# Sheet1.net
KiCad netlist of a schematic drawn in Altium Designer
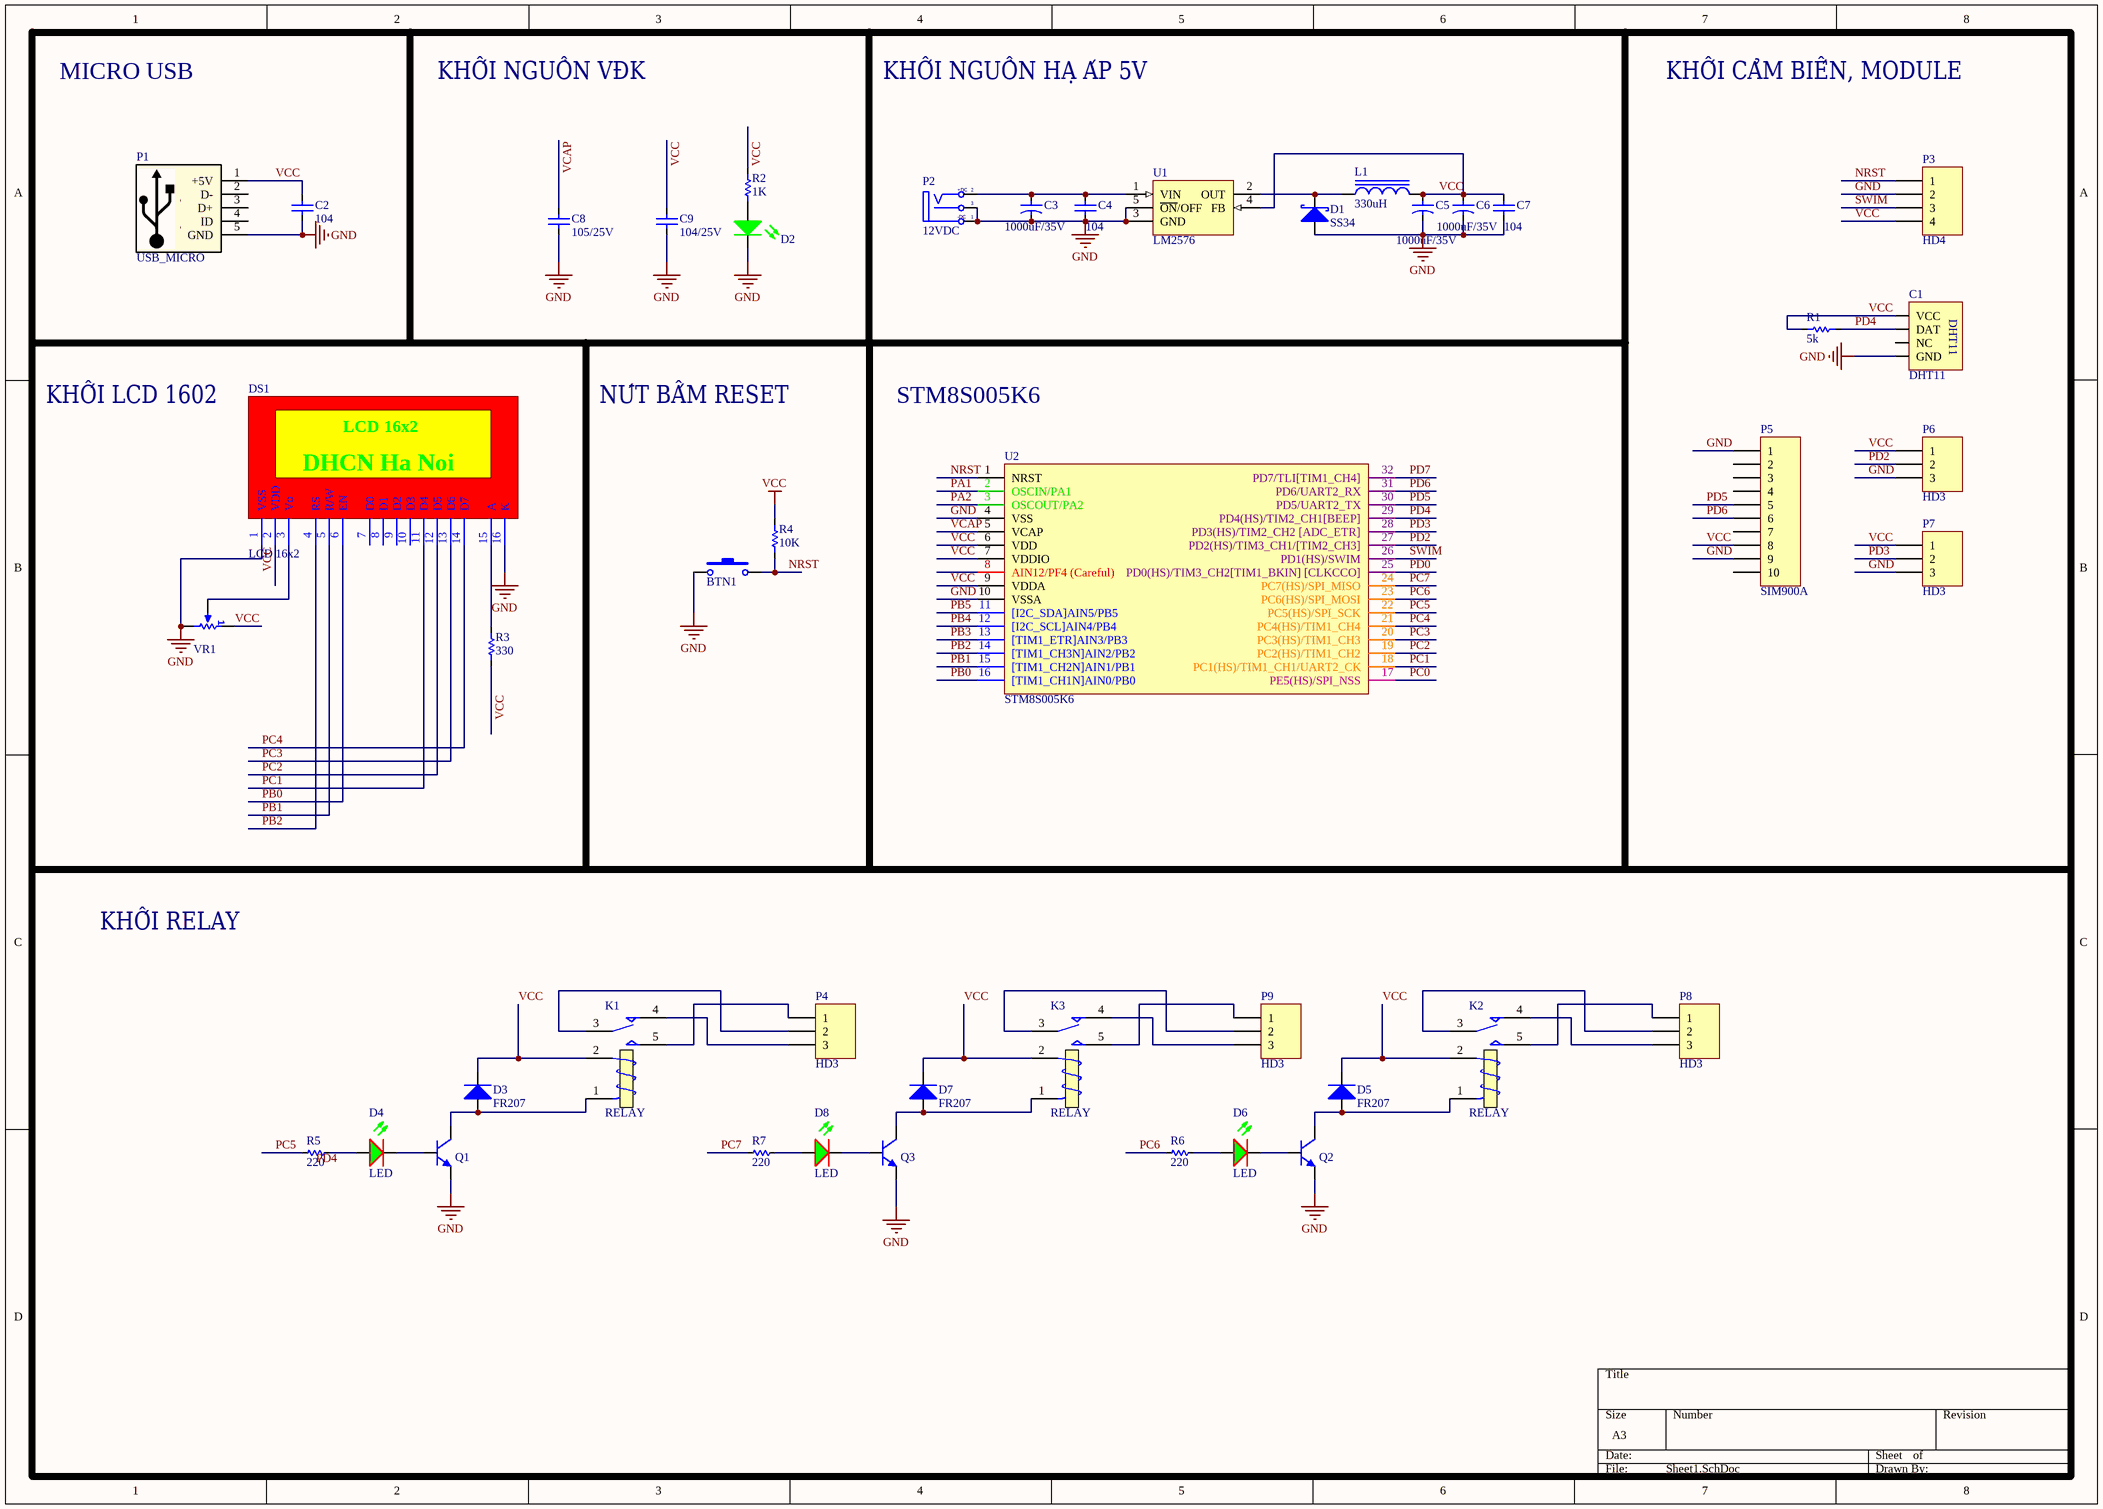
[diagram p0: Sheet1.SchDoc]

(export (version "E")
  (design (tool "Eeschema 10.0.6"))
  (components
    (comp (ref "BTN1")
      (value "BT")
      (footprint "BUTTON SMD MINI")
      (libsource (lib "LIB ALtium") (part "BUTTON"))
    )
    (comp (ref "C1")
      (value "DHT11")
      (footprint "DHT11")
      (fields
        (field (name "MANUFACTURER") "Würth Elektronik eiSos GmbH")
        (field (name "PARTNO") "613004143121")
        (field (name "CREATED BY") "Karrer Zheng")
      )
      (libsource (lib "LIBRARY") (part "DHT11"))
    )
    (comp (ref "C2")
      (value "104")
      (footprint "CAP-0805")
      (description "22pF ±5% 50V Ceramic Capacitor C0G, NP0 0805 (2012 Metric)")
      (fields
        (field (name "MANUFACTURER") "Samsung Electro-Mechanics America, Inc.")
        (field (name "MANUFACTURER PART NUMBER") "CL21B105KOFNNNE")
      )
      (libsource (lib "AltiumLibraryTieuBao") (part "CAP-CER-22pF-50V-0805-10%"))
    )
    (comp (ref "C3")
      (value "1000uF/35V")
      (footprint "CAP 13x25x5")
      (libsource (lib "AltiumLibraryTieuBao_moi") (part "CAP 1000uF/35V"))
    )
    (comp (ref "C4")
      (value "104")
      (footprint "CAP-0603")
      (description "1000pF 50V Ceramic Capacitor X7R 0603 (1608 Metric) 0.063\" L x 0.031\" W (1.60mm x 0.80mm)")
      (fields
        (field (name "MANUFACTURER") "Samsung Electro-Mechanics America, Inc.")
        (field (name "MANUFACTURER PART NUMBER") "CL10B102KB8NNNC")
      )
      (libsource (lib "AltiumLibraryTieuBao_moi") (part "CAP-CER-102-50V-0603-10%_6"))
    )
    (comp (ref "C5")
      (value "1000uF/35V")
      (footprint "CAP 13x25x5")
      (libsource (lib "AltiumLibraryTieuBao_moi") (part "CAP 1000uF/35V"))
    )
    (comp (ref "C6")
      (value "1000uF/35V")
      (footprint "CAP 13x25x5")
      (libsource (lib "AltiumLibraryTieuBao_moi") (part "CAP 1000uF/35V"))
    )
    (comp (ref "C7")
      (value "104")
      (footprint "CAP-0603")
      (description "1000pF 50V Ceramic Capacitor X7R 0603 (1608 Metric) 0.063\" L x 0.031\" W (1.60mm x 0.80mm)")
      (fields
        (field (name "MANUFACTURER") "Samsung Electro-Mechanics America, Inc.")
        (field (name "MANUFACTURER PART NUMBER") "CL10B102KB8NNNC")
      )
      (libsource (lib "AltiumLibraryTieuBao_moi") (part "CAP-CER-102-50V-0603-10%_6"))
    )
    (comp (ref "C8")
      (value "105/25V")
      (footprint "CAP-0805")
      (description "0.10µF ±10% 25V Ceramic Capacitor X7R 0805 (2012 Metric)")
      (fields
        (field (name "MANUFACTURER") "Samsung Electro-Mechanics America, Inc.")
        (field (name "MANUFACTURER PART NUMBER") "CL21B104KACNNNC")
      )
      (libsource (lib "AltiumLibraryTieuBao") (part "CAP-CER-104-25V-0805-10%"))
    )
    (comp (ref "C9")
      (value "104/25V")
      (footprint "CAP-0805")
      (description "0.10µF ±10% 25V Ceramic Capacitor X7R 0805 (2012 Metric)")
      (fields
        (field (name "MANUFACTURER") "Samsung Electro-Mechanics America, Inc.")
        (field (name "MANUFACTURER PART NUMBER") "CL21B104KACNNNC")
      )
      (libsource (lib "AltiumLibraryTieuBao") (part "CAP-CER-104-25V-0805-10%"))
    )
    (comp (ref "D1")
      (value "SS34")
      (footprint "DO-214AC")
      (description "Diode Schottky 40V 1A Surface Mount SMA (DO-214AC)")
      (fields
        (field (name "MANUFACTURER") "Fairchild Semiconductor")
        (field (name "MANUFACTURER PART NUMBER") "SS14")
      )
      (libsource (lib "AltiumLibraryTieuBao_moi") (part "SS14"))
    )
    (comp (ref "D2")
      (value "LED-G")
      (footprint "LED-0603-G")
      (description "Green 570nm LED Indication - Discrete 2.1V 0603 (1608 Metric)")
      (fields
        (field (name "MANUFACTURER") "Everlight Electronics Co Ltd")
        (field (name "MANUFACTURER PART NUMBER") "QTLP601C4TR")
      )
      (libsource (lib "LIB ALtium") (part "LED-0603-G"))
    )
    (comp (ref "D3")
      (value "FR207")
      (footprint "DO-41-300MIL-1N4007")
      (description "Diode Standard 1000V (1kV) 1A Surface Mount SMB")
      (fields
        (field (name "MANUFACTURER") "Diodes Incorporated")
        (field (name "MANUFACTURER PART NUMBER") "RS1MB-13")
      )
      (libsource (lib "LIB ALtium") (part "1N4007"))
    )
    (comp (ref "D4") (value "LED") (footprint "LED_5mm") (libsource (lib "LIB ALtium") (part "LED")))
    (comp (ref "D5")
      (value "FR207")
      (footprint "DO-41-300MIL-1N4007")
      (description "Diode Standard 1000V (1kV) 1A Surface Mount SMB")
      (fields
        (field (name "MANUFACTURER") "Diodes Incorporated")
        (field (name "MANUFACTURER PART NUMBER") "RS1MB-13")
      )
      (libsource (lib "LIB ALtium") (part "1N4007"))
    )
    (comp (ref "D6") (value "LED") (footprint "LED_5mm") (libsource (lib "LIB ALtium") (part "LED")))
    (comp (ref "D7")
      (value "FR207")
      (footprint "DO-41-300MIL-1N4007")
      (description "Diode Standard 1000V (1kV) 1A Surface Mount SMB")
      (fields
        (field (name "MANUFACTURER") "Diodes Incorporated")
        (field (name "MANUFACTURER PART NUMBER") "RS1MB-13")
      )
      (libsource (lib "LIB ALtium") (part "1N4007"))
    )
    (comp (ref "D8") (value "LED") (footprint "LED_5mm") (libsource (lib "LIB ALtium") (part "LED")))
    (comp (ref "DS1")
      (value "LCD 16x2")
      (footprint "LCD16x2_V1")
      (libsource (lib "AltiumLibraryTieuBao") (part "LCD TypeA"))
    )
    (comp (ref "K1")
      (value "RELAY")
      (footprint "RELAY 12V_112D1")
      (libsource (lib "LIB ALtium") (part "RELAY D"))
    )
    (comp (ref "K2")
      (value "RELAY")
      (footprint "RELAY 12V_112D1")
      (libsource (lib "LIB ALtium") (part "RELAY D"))
    )
    (comp (ref "K3")
      (value "RELAY")
      (footprint "RELAY 12V_112D1")
      (libsource (lib "LIB ALtium") (part "RELAY D"))
    )
    (comp (ref "L1")
      (value "330uH")
      (footprint "INDUCTOR 2")
      (libsource (lib "AltiumLibraryTieuBao_moi") (part "INDUCTOR"))
    )
    (comp (ref "P1")
      (value "USB_MICRO")
      (footprint "USB_MICRO")
      (libsource (lib "AltiumLibraryTieuBao") (part "USB_MICRO"))
    )
    (comp (ref "P2")
      (value "12VDC")
      (footprint "JACK DC 5.5x2")
      (description "Jac DC input")
      (fields (field (name "Comment") "JACK DC"))
      (libsource (lib "AltiumLibraryTieuBao_moi") (part "JACK DC"))
    )
    (comp (ref "P3")
      (value "HD4")
      (footprint "XH2.54-4A")
      (libsource (lib "AltiumLibraryTieuBao") (part "HEADER 4"))
    )
    (comp (ref "P4")
      (value "HD3")
      (footprint "CON 3")
      (libsource (lib "AltiumLibraryTieuBao") (part "HEADER 3"))
    )
    (comp (ref "P5")
      (value "SIM900A")
      (footprint "HD 10")
      (libsource (lib "AltiumLibraryTieuBao") (part "HEADER 10"))
    )
    (comp (ref "P6")
      (value "HD3")
      (footprint "JUMP 3")
      (libsource (lib "AltiumLibraryTieuBao") (part "HEADER 3"))
    )
    (comp (ref "P7")
      (value "HD3")
      (footprint "JUMP 3")
      (libsource (lib "AltiumLibraryTieuBao") (part "HEADER 3"))
    )
    (comp (ref "P8")
      (value "HD3")
      (footprint "CON 3")
      (libsource (lib "AltiumLibraryTieuBao") (part "HEADER 3"))
    )
    (comp (ref "P9")
      (value "HD3")
      (footprint "CON 3")
      (libsource (lib "AltiumLibraryTieuBao") (part "HEADER 3"))
    )
    (comp (ref "Q1") (value "C1815") (footprint "TO 92") (libsource (lib "LIB ALtium") (part "C1815-TO92")))
    (comp (ref "Q2") (value "C1815") (footprint "TO 92") (libsource (lib "LIB ALtium") (part "C1815-TO92")))
    (comp (ref "Q3") (value "C1815") (footprint "TO 92") (libsource (lib "LIB ALtium") (part "C1815-TO92")))
    (comp (ref "R1")
      (value "5k")
      (footprint "R-0805")
      (description "No Solder Or Re-Calculated")
      (libsource (lib "AltiumLibraryTieuBao") (part "R-0805"))
    )
    (comp (ref "R2")
      (value "1K")
      (footprint "R-0805-1K")
      (description "RES SMD 1K OHM 5% 1/8W 0805")
      (fields
        (field (name "MANUFACTURER") "Yageo")
        (field (name "MANUFACTURER PART NUMBER") "RC0805JR-071KL")
      )
      (libsource (lib "AltiumLibraryTieuBao") (part "R-0805/5%-1K"))
    )
    (comp (ref "R3")
      (value "330")
      (footprint "R-0805-1K")
      (description "RES SMD 1K OHM 5% 1/8W 0805")
      (fields
        (field (name "MANUFACTURER") "Yageo")
        (field (name "MANUFACTURER PART NUMBER") "RC0805JR-071KL")
      )
      (libsource (lib "AltiumLibraryTieuBao") (part "R-0805/5%-1K"))
    )
    (comp (ref "R4")
      (value "10K")
      (footprint "R-0805-1K")
      (description "RES SMD 1K OHM 5% 1/8W 0805")
      (fields
        (field (name "MANUFACTURER") "Yageo")
        (field (name "MANUFACTURER PART NUMBER") "RC0805JR-071KL")
      )
      (libsource (lib "AltiumLibraryTieuBao") (part "R-0805/5%-1K"))
    )
    (comp (ref "R5")
      (value "220")
      (footprint "RES-1/4W")
      (description "Res")
      (fields
        (field (name "MANUFACTURER") "Generic Components")
        (field (name "PUBLISHER") "Altium Hobart Technology Centre")
      )
      (libsource (lib "LIBRARY") (part "Res"))
    )
    (comp (ref "R6")
      (value "220")
      (footprint "RES-1/4W")
      (description "Res")
      (fields
        (field (name "MANUFACTURER") "Generic Components")
        (field (name "PUBLISHER") "Altium Hobart Technology Centre")
      )
      (libsource (lib "LIBRARY") (part "Res"))
    )
    (comp (ref "R7")
      (value "220")
      (footprint "RES-1/4W")
      (description "Res")
      (fields
        (field (name "MANUFACTURER") "Generic Components")
        (field (name "PUBLISHER") "Altium Hobart Technology Centre")
      )
      (libsource (lib "LIBRARY") (part "Res"))
    )
    (comp (ref "U1")
      (value "LM2576")
      (footprint "TO 263 [LM2576]")
      (libsource (lib "AltiumLibraryTieuBao_moi") (part "LM2576"))
    )
    (comp (ref "U2")
      (value "STM8S005K6")
      (footprint "LQFP-32-STM8S005K6")
      (description "STM8 STM8S Microcontroller IC 8-Bit 16MHz 32KB (32K x 8) FLASH 32-LQFP (7x7)")
      (fields
        (field (name "MANUFACTURER") "STMicroelectronics")
        (field (name "MANUFACTURER PART NUMBER") "STM8S005K6T6C")
      )
      (libsource (lib "AltiumLibraryTieuBao") (part "STM8S005K6"))
    )
    (comp (ref "VR1")
      (value "VR")
      (footprint "POT-3296W")
      (libsource (lib "AltiumLibraryTieuBao") (part "VR"))
    )
  )
  (nets
    (net (code "1") (name "/NRST") (class "Default")
      (node (ref "BTN1") (pin "2") (pinfunction "2_2") (pintype "passive"))
      (node (ref "P3") (pin "1") (pinfunction "1_1") (pintype "passive"))
      (node (ref "R4") (pin "1") (pinfunction "1_1") (pintype "passive"))
      (node (ref "U2") (pin "1") (pinfunction "NRST_1") (pintype "passive"))
    )
    (net (code "2") (name "/PA1") (class "Default")
      (node (ref "U2") (pin "2") (pinfunction "OSCIN/PA1_2") (pintype "passive"))
    )
    (net (code "3") (name "/PA2") (class "Default")
      (node (ref "U2") (pin "3") (pinfunction "OSCOUT/PA2_3") (pintype "passive"))
    )
    (net (code "4") (name "/PB0") (class "Default")
      (node (ref "DS1") (pin "6") (pinfunction "EN_6") (pintype "passive"))
      (node (ref "U2") (pin "16") (pinfunction "[TIM1_CH1N]AIN0/PB0_16") (pintype "passive"))
    )
    (net (code "5") (name "/PB1") (class "Default")
      (node (ref "DS1") (pin "5") (pinfunction "R/W_5") (pintype "passive"))
      (node (ref "U2") (pin "15") (pinfunction "[TIM1_CH2N]AIN1/PB1_15") (pintype "passive"))
    )
    (net (code "6") (name "/PB2") (class "Default")
      (node (ref "DS1") (pin "4") (pinfunction "RS_4") (pintype "passive"))
      (node (ref "U2") (pin "14") (pinfunction "[TIM1_CH3N]AIN2/PB2_14") (pintype "passive"))
    )
    (net (code "7") (name "/PB3") (class "Default")
      (node (ref "U2") (pin "13") (pinfunction "[TIM1_ETR]AIN3/PB3_13") (pintype "passive"))
    )
    (net (code "8") (name "/PB4") (class "Default")
      (node (ref "U2") (pin "12") (pinfunction "[I2C_SCL]AIN4/PB4_12") (pintype "passive"))
    )
    (net (code "9") (name "/PB5") (class "Default")
      (node (ref "U2") (pin "11") (pinfunction "[I2C_SDA]AIN5/PB5_11") (pintype "passive"))
    )
    (net (code "10") (name "/PC0") (class "Default")
      (node (ref "U2") (pin "17") (pinfunction "PE5(HS)/SPI_NSS_17") (pintype "passive"))
    )
    (net (code "11") (name "/PC1") (class "Default")
      (node (ref "DS1") (pin "11") (pinfunction "D4_11") (pintype "passive"))
      (node (ref "U2") (pin "18") (pinfunction "PC1(HS)/TIM1_CH1/UART2_CK_18") (pintype "passive"))
    )
    (net (code "12") (name "/PC2") (class "Default")
      (node (ref "DS1") (pin "12") (pinfunction "D5_12") (pintype "passive"))
      (node (ref "U2") (pin "19") (pinfunction "PC2(HS)/TIM1_CH2_19") (pintype "passive"))
    )
    (net (code "13") (name "/PC3") (class "Default")
      (node (ref "DS1") (pin "13") (pinfunction "D6_13") (pintype "passive"))
      (node (ref "U2") (pin "20") (pinfunction "PC3(HS)/TIM1_CH3_20") (pintype "passive"))
    )
    (net (code "14") (name "/PC4") (class "Default")
      (node (ref "DS1") (pin "14") (pinfunction "D7_14") (pintype "passive"))
      (node (ref "U2") (pin "21") (pinfunction "PC4(HS)/TIM1_CH4_21") (pintype "passive"))
    )
    (net (code "15") (name "/PC5") (class "Default")
      (node (ref "R5") (pin "1") (pinfunction "1_1") (pintype "passive"))
      (node (ref "U2") (pin "22") (pinfunction "PC5(HS)/SPI_SCK_22") (pintype "passive"))
    )
    (net (code "16") (name "/PC6") (class "Default")
      (node (ref "R6") (pin "1") (pinfunction "1_1") (pintype "passive"))
      (node (ref "U2") (pin "23") (pinfunction "PC6(HS)/SPI_MOSI_23") (pintype "passive"))
    )
    (net (code "17") (name "/PC7") (class "Default")
      (node (ref "R7") (pin "1") (pinfunction "1_1") (pintype "passive"))
      (node (ref "U2") (pin "24") (pinfunction "PC7(HS)/SPI_MISO_24") (pintype "passive"))
    )
    (net (code "18") (name "/PD0") (class "Default")
      (node (ref "U2") (pin "25") (pinfunction "PD0(HS)/TIM3_CH2[TIM1_BKIN]_[CLKCCO]_25") (pintype "passive"))
    )
    (net (code "19") (name "/PD2") (class "Default")
      (node (ref "P6") (pin "2") (pinfunction "2_2") (pintype "passive"))
      (node (ref "U2") (pin "27") (pinfunction "PD2(HS)/TIM3_CH1/[TIM2_CH3]_27") (pintype "passive"))
    )
    (net (code "20") (name "/PD3") (class "Default")
      (node (ref "P7") (pin "2") (pinfunction "2_2") (pintype "passive"))
      (node (ref "U2") (pin "28") (pinfunction "PD3(HS)/TIM2_CH2_[ADC_ETR]_28") (pintype "passive"))
    )
    (net (code "21") (name "/PD4") (class "Default")
      (node (ref "C1") (pin "2") (pinfunction "DAT_2") (pintype "passive"))
      (node (ref "R1") (pin "2") (pinfunction "2_2") (pintype "passive"))
      (node (ref "U2") (pin "29") (pinfunction "PD4(HS)/TIM2_CH1[BEEP]_29") (pintype "passive"))
    )
    (net (code "22") (name "/PD5") (class "Default")
      (node (ref "P5") (pin "5") (pinfunction "5_5") (pintype "passive"))
      (node (ref "U2") (pin "30") (pinfunction "PD5/UART2_TX_30") (pintype "passive"))
    )
    (net (code "23") (name "/PD6") (class "Default")
      (node (ref "P5") (pin "6") (pinfunction "6_6") (pintype "passive"))
      (node (ref "U2") (pin "31") (pinfunction "PD6/UART2_RX_31") (pintype "passive"))
    )
    (net (code "24") (name "/PD7") (class "Default")
      (node (ref "U2") (pin "32") (pinfunction "PD7/TLI[TIM1_CH4]_32") (pintype "passive"))
    )
    (net (code "25") (name "/SWIM") (class "Default")
      (node (ref "P3") (pin "3") (pinfunction "3_3") (pintype "passive"))
      (node (ref "U2") (pin "26") (pinfunction "PD1(HS)/SWIM_26") (pintype "passive"))
    )
    (net (code "26") (name "/VCAP") (class "Default")
      (node (ref "C8") (pin "1") (pinfunction "1_1") (pintype "passive"))
      (node (ref "U2") (pin "5") (pinfunction "VCAP_5") (pintype "passive"))
    )
    (net (code "27") (name "GND") (class "Default")
      (node (ref "BTN1") (pin "1") (pinfunction "1_1") (pintype "passive"))
      (node (ref "C1") (pin "4") (pinfunction "GND_4") (pintype "passive"))
      (node (ref "C2") (pin "2") (pinfunction "2_2") (pintype "passive"))
      (node (ref "C3") (pin "2") (pinfunction "2_2") (pintype "passive"))
      (node (ref "C4") (pin "2") (pinfunction "2_2") (pintype "passive"))
      (node (ref "C5") (pin "2") (pinfunction "2_2") (pintype "passive"))
      (node (ref "C6") (pin "2") (pinfunction "2_2") (pintype "passive"))
      (node (ref "C7") (pin "2") (pinfunction "2_2") (pintype "passive"))
      (node (ref "C8") (pin "2") (pinfunction "2_2") (pintype "passive"))
      (node (ref "C9") (pin "2") (pinfunction "2_2") (pintype "passive"))
      (node (ref "D1") (pin "1") (pinfunction "A_1") (pintype "passive"))
      (node (ref "D2") (pin "2") (pinfunction "K_2") (pintype "passive"))
      (node (ref "DS1") (pin "1") (pinfunction "VSS_1") (pintype "passive"))
      (node (ref "DS1") (pin "16") (pinfunction "K_16") (pintype "passive"))
      (node (ref "P1") (pin "5") (pinfunction "GND_5") (pintype "passive"))
      (node (ref "P2") (pin "1") (pinfunction "T_1") (pintype "passive"))
      (node (ref "P2") (pin "3") (pinfunction "S_3") (pintype "power_in"))
      (node (ref "P3") (pin "2") (pinfunction "2_2") (pintype "passive"))
      (node (ref "P5") (pin "1") (pinfunction "1_1") (pintype "passive"))
      (node (ref "P5") (pin "9") (pinfunction "9_9") (pintype "passive"))
      (node (ref "P6") (pin "3") (pinfunction "3_3") (pintype "passive"))
      (node (ref "P7") (pin "3") (pinfunction "3_3") (pintype "passive"))
      (node (ref "Q1") (pin "1") (pinfunction "E_1") (pintype "passive"))
      (node (ref "Q2") (pin "1") (pinfunction "E_1") (pintype "passive"))
      (node (ref "Q3") (pin "1") (pinfunction "E_1") (pintype "passive"))
      (node (ref "U1") (pin "3") (pinfunction "GND_3") (pintype "power_in"))
      (node (ref "U1") (pin "5") (pinfunction "~{ON}/OFF_5") (pintype "passive"))
      (node (ref "U2") (pin "10") (pinfunction "VSSA_10") (pintype "passive"))
      (node (ref "U2") (pin "4") (pinfunction "VSS_4") (pintype "passive"))
      (node (ref "VR1") (pin "3") (pinfunction "BOT_3") (pintype "passive"))
    )
    (net (code "28") (name "Net-(D1-K)") (class "Default")
      (node (ref "D1") (pin "2") (pinfunction "K_2") (pintype "passive"))
      (node (ref "L1") (pin "1") (pinfunction "1_1") (pintype "passive"))
      (node (ref "U1") (pin "2") (pinfunction "OUT_2") (pintype "open_emitter"))
    )
    (net (code "29") (name "Net-(D2-A)") (class "Default")
      (node (ref "D2") (pin "1") (pinfunction "A_1") (pintype "passive"))
      (node (ref "R2") (pin "1") (pinfunction "1_1") (pintype "passive"))
    )
    (net (code "30") (name "Net-(D3-A)") (class "Default")
      (node (ref "D3") (pin "1") (pinfunction "A_1") (pintype "passive"))
      (node (ref "K1") (pin "1") (pinfunction "T2_1") (pintype "passive"))
      (node (ref "Q1") (pin "2") (pinfunction "C_2") (pintype "passive"))
    )
    (net (code "31") (name "Net-(D4-A)") (class "Default")
      (node (ref "D4") (pin "1") (pinfunction "A_1") (pintype "passive"))
      (node (ref "R5") (pin "2") (pinfunction "2_2") (pintype "passive"))
    )
    (net (code "32") (name "Net-(D4-K)") (class "Default")
      (node (ref "D4") (pin "2") (pinfunction "K_2") (pintype "passive"))
      (node (ref "Q1") (pin "3") (pinfunction "B_3") (pintype "passive"))
    )
    (net (code "33") (name "Net-(D5-A)") (class "Default")
      (node (ref "D5") (pin "1") (pinfunction "A_1") (pintype "passive"))
      (node (ref "K2") (pin "1") (pinfunction "T2_1") (pintype "passive"))
      (node (ref "Q2") (pin "2") (pinfunction "C_2") (pintype "passive"))
    )
    (net (code "34") (name "Net-(D6-A)") (class "Default")
      (node (ref "D6") (pin "1") (pinfunction "A_1") (pintype "passive"))
      (node (ref "R6") (pin "2") (pinfunction "2_2") (pintype "passive"))
    )
    (net (code "35") (name "Net-(D6-K)") (class "Default")
      (node (ref "D6") (pin "2") (pinfunction "K_2") (pintype "passive"))
      (node (ref "Q2") (pin "3") (pinfunction "B_3") (pintype "passive"))
    )
    (net (code "36") (name "Net-(D7-A)") (class "Default")
      (node (ref "D7") (pin "1") (pinfunction "A_1") (pintype "passive"))
      (node (ref "K3") (pin "1") (pinfunction "T2_1") (pintype "passive"))
      (node (ref "Q3") (pin "2") (pinfunction "C_2") (pintype "passive"))
    )
    (net (code "37") (name "Net-(D8-A)") (class "Default")
      (node (ref "D8") (pin "1") (pinfunction "A_1") (pintype "passive"))
      (node (ref "R7") (pin "2") (pinfunction "2_2") (pintype "passive"))
    )
    (net (code "38") (name "Net-(D8-K)") (class "Default")
      (node (ref "D8") (pin "2") (pinfunction "K_2") (pintype "passive"))
      (node (ref "Q3") (pin "3") (pinfunction "B_3") (pintype "passive"))
    )
    (net (code "39") (name "Net-(DS1-A)") (class "Default")
      (node (ref "DS1") (pin "15") (pinfunction "A_15") (pintype "passive"))
      (node (ref "R3") (pin "2") (pinfunction "2_2") (pintype "passive"))
    )
    (net (code "40") (name "Net-(DS1-Vo)") (class "Default")
      (node (ref "DS1") (pin "3") (pinfunction "Vo_3") (pintype "passive"))
      (node (ref "VR1") (pin "2") (pinfunction "TAP_2") (pintype "passive"))
    )
    (net (code "41") (name "Net-(K1-COM)") (class "Default")
      (node (ref "K1") (pin "3") (pinfunction "COM_3") (pintype "passive"))
      (node (ref "P4") (pin "2") (pinfunction "2_2") (pintype "passive"))
    )
    (net (code "42") (name "Net-(K1-NC)") (class "Default")
      (node (ref "K1") (pin "4") (pinfunction "NC_4") (pintype "passive"))
      (node (ref "P4") (pin "3") (pinfunction "3_3") (pintype "passive"))
    )
    (net (code "43") (name "Net-(K1-NO)") (class "Default")
      (node (ref "K1") (pin "5") (pinfunction "NO_5") (pintype "passive"))
      (node (ref "P4") (pin "1") (pinfunction "1_1") (pintype "passive"))
    )
    (net (code "44") (name "Net-(K2-COM)") (class "Default")
      (node (ref "K2") (pin "3") (pinfunction "COM_3") (pintype "passive"))
      (node (ref "P8") (pin "2") (pinfunction "2_2") (pintype "passive"))
    )
    (net (code "45") (name "Net-(K2-NC)") (class "Default")
      (node (ref "K2") (pin "4") (pinfunction "NC_4") (pintype "passive"))
      (node (ref "P8") (pin "3") (pinfunction "3_3") (pintype "passive"))
    )
    (net (code "46") (name "Net-(K2-NO)") (class "Default")
      (node (ref "K2") (pin "5") (pinfunction "NO_5") (pintype "passive"))
      (node (ref "P8") (pin "1") (pinfunction "1_1") (pintype "passive"))
    )
    (net (code "47") (name "Net-(K3-COM)") (class "Default")
      (node (ref "K3") (pin "3") (pinfunction "COM_3") (pintype "passive"))
      (node (ref "P9") (pin "2") (pinfunction "2_2") (pintype "passive"))
    )
    (net (code "48") (name "Net-(K3-NC)") (class "Default")
      (node (ref "K3") (pin "4") (pinfunction "NC_4") (pintype "passive"))
      (node (ref "P9") (pin "3") (pinfunction "3_3") (pintype "passive"))
    )
    (net (code "49") (name "Net-(K3-NO)") (class "Default")
      (node (ref "K3") (pin "5") (pinfunction "NO_5") (pintype "passive"))
      (node (ref "P9") (pin "1") (pinfunction "1_1") (pintype "passive"))
    )
    (net (code "50") (name "Net-(P2-TN)") (class "Default")
      (node (ref "C3") (pin "1") (pinfunction "1_1") (pintype "passive"))
      (node (ref "C4") (pin "1") (pinfunction "1_1") (pintype "passive"))
      (node (ref "P2") (pin "2") (pinfunction "TN_2") (pintype "passive"))
      (node (ref "U1") (pin "1") (pinfunction "VIN_1") (pintype "input"))
    )
    (net (code "51") (name "VCC") (class "Default")
      (node (ref "C1") (pin "1") (pinfunction "VCC_1") (pintype "passive"))
      (node (ref "C2") (pin "1") (pinfunction "1_1") (pintype "passive"))
      (node (ref "C5") (pin "1") (pinfunction "1_1") (pintype "passive"))
      (node (ref "C6") (pin "1") (pinfunction "1_1") (pintype "passive"))
      (node (ref "C7") (pin "1") (pinfunction "1_1") (pintype "passive"))
      (node (ref "C9") (pin "1") (pinfunction "1_1") (pintype "passive"))
      (node (ref "D3") (pin "2") (pinfunction "K_2") (pintype "passive"))
      (node (ref "D5") (pin "2") (pinfunction "K_2") (pintype "passive"))
      (node (ref "D7") (pin "2") (pinfunction "K_2") (pintype "passive"))
      (node (ref "DS1") (pin "2") (pinfunction "VDD_2") (pintype "passive"))
      (node (ref "K1") (pin "2") (pinfunction "T1_2") (pintype "passive"))
      (node (ref "K2") (pin "2") (pinfunction "T1_2") (pintype "passive"))
      (node (ref "K3") (pin "2") (pinfunction "T1_2") (pintype "passive"))
      (node (ref "L1") (pin "2") (pinfunction "2_2") (pintype "passive"))
      (node (ref "P1") (pin "1") (pinfunction "+5V_1") (pintype "passive"))
      (node (ref "P3") (pin "4") (pinfunction "4_4") (pintype "passive"))
      (node (ref "P5") (pin "8") (pinfunction "8_8") (pintype "passive"))
      (node (ref "P6") (pin "1") (pinfunction "1_1") (pintype "passive"))
      (node (ref "P7") (pin "1") (pinfunction "1_1") (pintype "passive"))
      (node (ref "R1") (pin "1") (pinfunction "1_1") (pintype "passive"))
      (node (ref "R2") (pin "2") (pinfunction "2_2") (pintype "passive"))
      (node (ref "R3") (pin "1") (pinfunction "1_1") (pintype "passive"))
      (node (ref "R4") (pin "2") (pinfunction "2_2") (pintype "passive"))
      (node (ref "U1") (pin "4") (pinfunction "FB_4") (pintype "input"))
      (node (ref "U2") (pin "6") (pinfunction "VDD_6") (pintype "passive"))
      (node (ref "U2") (pin "7") (pinfunction "VDDIO_7") (pintype "passive"))
      (node (ref "U2") (pin "9") (pinfunction "VDDA_9") (pintype "passive"))
      (node (ref "VR1") (pin "1") (pinfunction "TOP_1") (pintype "passive"))
    )
    (net (code "52") (name "unconnected-(C1-NC-Pad3)") (class "Default")
      (node (ref "C1") (pin "3") (pinfunction "NC_3") (pintype "passive"))
    )
    (net (code "53") (name "unconnected-(DS1-D0-Pad7)") (class "Default")
      (node (ref "DS1") (pin "7") (pinfunction "D0_7") (pintype "passive"))
    )
    (net (code "54") (name "unconnected-(DS1-D1-Pad8)") (class "Default")
      (node (ref "DS1") (pin "8") (pinfunction "D1_8") (pintype "passive"))
    )
    (net (code "55") (name "unconnected-(DS1-D2-Pad9)") (class "Default")
      (node (ref "DS1") (pin "9") (pinfunction "D2_9") (pintype "passive"))
    )
    (net (code "56") (name "unconnected-(DS1-D3-Pad10)") (class "Default")
      (node (ref "DS1") (pin "10") (pinfunction "D3_10") (pintype "passive"))
    )
    (net (code "57") (name "unconnected-(P1-D+-Pad3)") (class "Default")
      (node (ref "P1") (pin "3") (pinfunction "D+_3") (pintype "passive"))
    )
    (net (code "58") (name "unconnected-(P1-D--Pad2)") (class "Default")
      (node (ref "P1") (pin "2") (pinfunction "D-_2") (pintype "passive"))
    )
    (net (code "59") (name "unconnected-(P1-ID-Pad4)") (class "Default")
      (node (ref "P1") (pin "4") (pinfunction "ID_4") (pintype "passive"))
    )
    (net (code "60") (name "unconnected-(P5-Pad2)") (class "Default")
      (node (ref "P5") (pin "2") (pinfunction "2_2") (pintype "passive"))
    )
    (net (code "61") (name "unconnected-(P5-Pad3)") (class "Default")
      (node (ref "P5") (pin "3") (pinfunction "3_3") (pintype "passive"))
    )
    (net (code "62") (name "unconnected-(P5-Pad4)") (class "Default")
      (node (ref "P5") (pin "4") (pinfunction "4_4") (pintype "passive"))
    )
    (net (code "63") (name "unconnected-(P5-Pad7)") (class "Default")
      (node (ref "P5") (pin "7") (pinfunction "7_7") (pintype "passive"))
    )
    (net (code "64") (name "unconnected-(P5-Pad10)") (class "Default")
      (node (ref "P5") (pin "10") (pinfunction "10_10") (pintype "passive"))
    )
    (net (code "65") (name "unconnected-(U2-AIN12{slash}PF4_(Careful)-Pad8)") (class "Default")
      (node (ref "U2") (pin "8") (pinfunction "AIN12/PF4_(Careful)_8") (pintype "passive"))
    )
  )
)
